# Placa_de_Cima.net
KiCad netlist of a schematic drawn in EAGLE
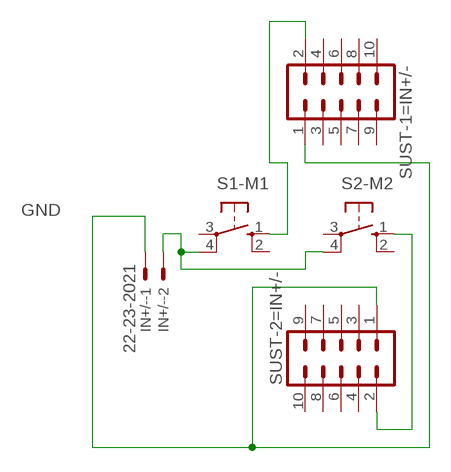
[diagram p0: schematic, sheet 1]

(export (version "E")
  (design (tool "Eeschema 10.0.6"))
  (components
    (comp (ref "IN+/-")
      (value "22-23-2021")
      (footprint "eagle-import:22-23-2021")
      (fields (field (name "MF") "MOLEX"))
      (libsource (lib "eagle-import") (part "22-23-2021"))
    )
    (comp (ref "S1-M1")
      (value "10-XX")
      (footprint "eagle-import:B3F-10XX")
      (fields (field (name "MPN") "B3F-1000"))
      (libsource (lib "eagle-import") (part "10-XX"))
    )
    (comp (ref "S2-M2")
      (value "10-XX")
      (footprint "eagle-import:B3F-10XX")
      (fields (field (name "MPN") "B3F-1000"))
      (libsource (lib "eagle-import") (part "10-XX"))
    )
    (comp (ref "SUST-1=IN+/-")
      (value "MA05-2")
      (footprint "eagle-import:MA05-2")
      (libsource (lib "eagle-import") (part "MA05-2"))
    )
    (comp (ref "SUST-2=IN+/-")
      (value "MA05-2")
      (footprint "eagle-import:MA05-2")
      (libsource (lib "eagle-import") (part "MA05-2"))
    )
  )
  (nets
    (net (code "1") (name "/GND") (class "Default")
      (node (ref "IN+/-") (pin "1") (pinfunction "S_1") (pintype "passive"))
      (node (ref "SUST-1=IN+/-") (pin "1") (pinfunction "1_1") (pintype "passive"))
      (node (ref "SUST-2=IN+/-") (pin "1") (pinfunction "1_1") (pintype "passive"))
    )
    (net (code "2") (name "Net-(IN+/-B-S)") (class "Default")
      (node (ref "IN+/-") (pin "2") (pinfunction "S_2") (pintype "passive"))
      (node (ref "S1-M1") (pin "4") (pinfunction "P1_4") (pintype "passive"))
      (node (ref "S2-M2") (pin "4") (pinfunction "P1_4") (pintype "passive"))
    )
    (net (code "3") (name "Net-(S1-M1-S)") (class "Default")
      (node (ref "S1-M1") (pin "1") (pinfunction "S_1") (pintype "passive"))
      (node (ref "SUST-1=IN+/-") (pin "2") (pinfunction "2_2") (pintype "passive"))
    )
    (net (code "4") (name "Net-(S2-M2-S)") (class "Default")
      (node (ref "S2-M2") (pin "1") (pinfunction "S_1") (pintype "passive"))
      (node (ref "SUST-2=IN+/-") (pin "2") (pinfunction "2_2") (pintype "passive"))
    )
    (net (code "5") (name "unconnected-(S1-M1-P-Pad3)") (class "Default")
      (node (ref "S1-M1") (pin "3") (pinfunction "P_3") (pintype "passive"))
    )
    (net (code "6") (name "unconnected-(S1-M1-S1-Pad2)") (class "Default")
      (node (ref "S1-M1") (pin "2") (pinfunction "S1_2") (pintype "passive"))
    )
    (net (code "7") (name "unconnected-(S2-M2-P-Pad3)") (class "Default")
      (node (ref "S2-M2") (pin "3") (pinfunction "P_3") (pintype "passive"))
    )
    (net (code "8") (name "unconnected-(S2-M2-S1-Pad2)") (class "Default")
      (node (ref "S2-M2") (pin "2") (pinfunction "S1_2") (pintype "passive"))
    )
    (net (code "9") (name "unconnected-(SUST-1=IN+/--Pad3)") (class "Default")
      (node (ref "SUST-1=IN+/-") (pin "3") (pinfunction "3_3") (pintype "passive"))
    )
    (net (code "10") (name "unconnected-(SUST-1=IN+/--Pad4)") (class "Default")
      (node (ref "SUST-1=IN+/-") (pin "4") (pinfunction "4_4") (pintype "passive"))
    )
    (net (code "11") (name "unconnected-(SUST-1=IN+/--Pad5)") (class "Default")
      (node (ref "SUST-1=IN+/-") (pin "5") (pinfunction "5_5") (pintype "passive"))
    )
    (net (code "12") (name "unconnected-(SUST-1=IN+/--Pad6)") (class "Default")
      (node (ref "SUST-1=IN+/-") (pin "6") (pinfunction "6_6") (pintype "passive"))
    )
    (net (code "13") (name "unconnected-(SUST-1=IN+/--Pad7)") (class "Default")
      (node (ref "SUST-1=IN+/-") (pin "7") (pinfunction "7_7") (pintype "passive"))
    )
    (net (code "14") (name "unconnected-(SUST-1=IN+/--Pad8)") (class "Default")
      (node (ref "SUST-1=IN+/-") (pin "8") (pinfunction "8_8") (pintype "passive"))
    )
    (net (code "15") (name "unconnected-(SUST-1=IN+/--Pad9)") (class "Default")
      (node (ref "SUST-1=IN+/-") (pin "9") (pinfunction "9_9") (pintype "passive"))
    )
    (net (code "16") (name "unconnected-(SUST-1=IN+/--Pad10)") (class "Default")
      (node (ref "SUST-1=IN+/-") (pin "10") (pinfunction "10_10") (pintype "passive"))
    )
    (net (code "17") (name "unconnected-(SUST-2=IN+/--Pad3)") (class "Default")
      (node (ref "SUST-2=IN+/-") (pin "3") (pinfunction "3_3") (pintype "passive"))
    )
    (net (code "18") (name "unconnected-(SUST-2=IN+/--Pad4)") (class "Default")
      (node (ref "SUST-2=IN+/-") (pin "4") (pinfunction "4_4") (pintype "passive"))
    )
    (net (code "19") (name "unconnected-(SUST-2=IN+/--Pad5)") (class "Default")
      (node (ref "SUST-2=IN+/-") (pin "5") (pinfunction "5_5") (pintype "passive"))
    )
    (net (code "20") (name "unconnected-(SUST-2=IN+/--Pad6)") (class "Default")
      (node (ref "SUST-2=IN+/-") (pin "6") (pinfunction "6_6") (pintype "passive"))
    )
    (net (code "21") (name "unconnected-(SUST-2=IN+/--Pad7)") (class "Default")
      (node (ref "SUST-2=IN+/-") (pin "7") (pinfunction "7_7") (pintype "passive"))
    )
    (net (code "22") (name "unconnected-(SUST-2=IN+/--Pad8)") (class "Default")
      (node (ref "SUST-2=IN+/-") (pin "8") (pinfunction "8_8") (pintype "passive"))
    )
    (net (code "23") (name "unconnected-(SUST-2=IN+/--Pad9)") (class "Default")
      (node (ref "SUST-2=IN+/-") (pin "9") (pinfunction "9_9") (pintype "passive"))
    )
    (net (code "24") (name "unconnected-(SUST-2=IN+/--Pad10)") (class "Default")
      (node (ref "SUST-2=IN+/-") (pin "10") (pinfunction "10_10") (pintype "passive"))
    )
  )
)
